# STLink.net
KiCad netlist of a schematic drawn in Altium Designer
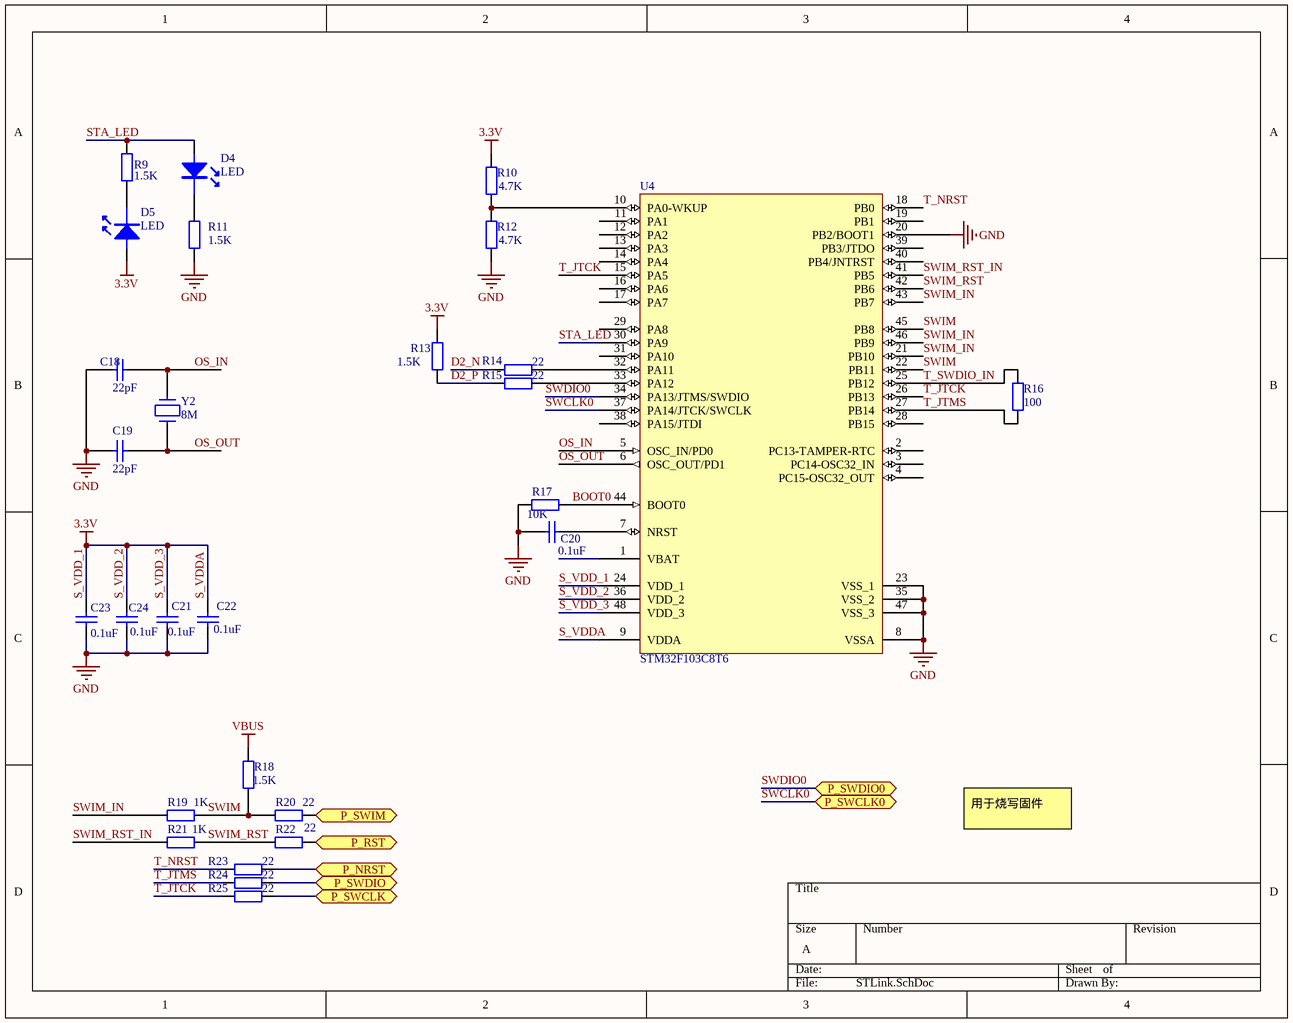
[diagram p0: STLink.SchDoc]

(export (version "E")
  (design (tool "Eeschema 10.0.6"))
  (components
    (comp (ref "C18")
      (value "22pF")
      (footprint "C-0603")
      (fields (field (name "Comment") "Cap"))
      (libsource (lib "WK_PCB") (part "Cap"))
    )
    (comp (ref "C19")
      (value "22pF")
      (footprint "C-0603")
      (fields (field (name "Comment") "Cap"))
      (libsource (lib "WK_PCB") (part "Cap"))
    )
    (comp (ref "C20")
      (value "0.1uF")
      (footprint "C-0603")
      (fields (field (name "Comment") "Cap"))
      (libsource (lib "WK_PCB") (part "Cap"))
    )
    (comp (ref "C21")
      (value "0.1uF")
      (footprint "C-0603")
      (description "Capacitor")
      (fields (field (name "Comment") "Cap") (field (name "PUBLISHER") "Altium Limited"))
      (libsource (lib "Miscellaneous Devices") (part "Cap"))
    )
    (comp (ref "C22")
      (value "0.1uF")
      (footprint "C-0603")
      (description "Capacitor")
      (fields (field (name "Comment") "Cap") (field (name "PUBLISHER") "Altium Limited"))
      (libsource (lib "Miscellaneous Devices") (part "Cap"))
    )
    (comp (ref "C23")
      (value "0.1uF")
      (footprint "C-0603")
      (description "Capacitor")
      (fields (field (name "Comment") "Cap") (field (name "PUBLISHER") "Altium Limited"))
      (libsource (lib "Miscellaneous Devices") (part "Cap"))
    )
    (comp (ref "C24")
      (value "0.1uF")
      (footprint "C-0603")
      (description "Capacitor")
      (fields (field (name "Comment") "Cap") (field (name "PUBLISHER") "Altium Limited"))
      (libsource (lib "Miscellaneous Devices") (part "Cap"))
    )
    (comp (ref "D4")
      (value "LED")
      (footprint "SMT_LED_0603")
      (description "LED 发光二极管")
      (libsource (lib "WK_PCB") (part "LED"))
    )
    (comp (ref "D5")
      (value "LED")
      (footprint "SMT_LED_0603")
      (description "LED 发光二极管")
      (libsource (lib "WK_PCB") (part "LED"))
    )
    (comp (ref "R9")
      (value "1.5K")
      (footprint "0603-1")
      (description "Resistor")
      (fields (field (name "Comment") "Res2") (field (name "PUBLISHER") "Altium Limited"))
      (libsource (lib "Miscellaneous Devices") (part "Res2"))
    )
    (comp (ref "R10")
      (value "4.7K")
      (footprint "0603-1")
      (description "Resistor")
      (fields (field (name "Comment") "Res2") (field (name "PUBLISHER") "Altium Limited"))
      (libsource (lib "Miscellaneous Devices") (part "Res2"))
    )
    (comp (ref "R11")
      (value "1.5K")
      (footprint "0603-1")
      (description "Resistor")
      (fields (field (name "Comment") "Res2") (field (name "PUBLISHER") "Altium Limited"))
      (libsource (lib "Miscellaneous Devices") (part "Res2"))
    )
    (comp (ref "R12")
      (value "4.7K")
      (footprint "0603-1")
      (description "Resistor")
      (fields (field (name "Comment") "Res2") (field (name "PUBLISHER") "Altium Limited"))
      (libsource (lib "Miscellaneous Devices") (part "Res2"))
    )
    (comp (ref "R13")
      (value "1.5K")
      (footprint "0603-1")
      (description "Resistor")
      (fields (field (name "Comment") "Res2") (field (name "PUBLISHER") "Altium Limited"))
      (libsource (lib "Miscellaneous Devices") (part "Res2"))
    )
    (comp (ref "R14")
      (value "22")
      (footprint "0603-1")
      (description "Resistor")
      (fields (field (name "Comment") "Res2") (field (name "PUBLISHER") "Altium Limited"))
      (libsource (lib "") (part "Res2_1"))
    )
    (comp (ref "R15")
      (value "22")
      (footprint "0603-1")
      (description "Resistor")
      (fields (field (name "Comment") "Res2") (field (name "PUBLISHER") "Altium Limited"))
      (libsource (lib "") (part "Res2_1"))
    )
    (comp (ref "R16")
      (value "100")
      (footprint "0603-1")
      (description "Resistor")
      (fields (field (name "Comment") "Res2") (field (name "PUBLISHER") "Altium Limited"))
      (libsource (lib "Miscellaneous Devices") (part "Res2"))
    )
    (comp (ref "R17")
      (value "10K")
      (footprint "0603-1")
      (description "Resistor")
      (fields (field (name "Comment") "Res2") (field (name "PUBLISHER") "Altium Limited"))
      (libsource (lib "") (part "Res2_1"))
    )
    (comp (ref "R18")
      (value "1.5K")
      (footprint "0603-1")
      (description "Resistor")
      (fields (field (name "Comment") "Res2") (field (name "PUBLISHER") "Altium Limited"))
      (libsource (lib "Miscellaneous Devices") (part "Res2"))
    )
    (comp (ref "R19")
      (value "1K")
      (footprint "0603-1")
      (description "Resistor")
      (fields (field (name "Comment") "Res2") (field (name "PUBLISHER") "Altium Limited"))
      (libsource (lib "") (part "Res2_1"))
    )
    (comp (ref "R20")
      (value "22")
      (footprint "0603-1")
      (description "Resistor")
      (fields (field (name "Comment") "Res2") (field (name "PUBLISHER") "Altium Limited"))
      (libsource (lib "") (part "Res2_1"))
    )
    (comp (ref "R21")
      (value "1K")
      (footprint "0603-1")
      (description "Resistor")
      (fields (field (name "Comment") "Res2") (field (name "PUBLISHER") "Altium Limited"))
      (libsource (lib "") (part "Res2_1"))
    )
    (comp (ref "R22")
      (value "22")
      (footprint "0603-1")
      (description "Resistor")
      (fields (field (name "Comment") "Res2") (field (name "PUBLISHER") "Altium Limited"))
      (libsource (lib "") (part "Res2_1"))
    )
    (comp (ref "R23")
      (value "22")
      (footprint "0603-1")
      (description "Resistor")
      (fields (field (name "Comment") "Res2") (field (name "PUBLISHER") "Altium Limited"))
      (libsource (lib "") (part "Res2_1"))
    )
    (comp (ref "R24")
      (value "22")
      (footprint "0603-1")
      (description "Resistor")
      (fields (field (name "Comment") "Res2") (field (name "PUBLISHER") "Altium Limited"))
      (libsource (lib "") (part "Res2_1"))
    )
    (comp (ref "R25")
      (value "22")
      (footprint "0603-1")
      (description "Resistor")
      (fields (field (name "Comment") "Res2") (field (name "PUBLISHER") "Altium Limited"))
      (libsource (lib "") (part "Res2_1"))
    )
    (comp (ref "U4")
      (value "STM32F103C8T6")
      (footprint "LQFP48_N")
      (description "STM32 ARM-based 32-bit MCU with 64 Kbytes Flash, 48-pin LQFP, Industrial Temperature")
      (fields (field (name "PUBLISHER") "Altium Limited"))
      (libsource (lib "ST Microcontroller 32-Bit STM32") (part "STM32F103C8T6"))
    )
    (comp (ref "Y2") (value "8M") (footprint "XAL5032 2-Leads") (libsource (lib "WK_PCB") (part "XTAL")))
  )
  (nets
    (net (code "1") (name "/BOOT0") (class "Default")
      (node (ref "R17") (pin "2") (pinfunction "2_2") (pintype "passive"))
      (node (ref "U4") (pin "44") (pinfunction "BOOT0_44") (pintype "input"))
    )
    (net (code "2") (name "/D2_N") (class "Default")
      (node (ref "R14") (pin "1") (pinfunction "1_1") (pintype "passive"))
    )
    (net (code "3") (name "/D2_P") (class "Default")
      (node (ref "R13") (pin "1") (pinfunction "1_1") (pintype "passive"))
      (node (ref "R15") (pin "1") (pinfunction "1_1") (pintype "passive"))
    )
    (net (code "4") (name "/OS_IN") (class "Default")
      (node (ref "C18") (pin "2") (pinfunction "2_2") (pintype "passive"))
      (node (ref "U4") (pin "5") (pinfunction "OSC_IN/PD0_5") (pintype "input"))
      (node (ref "Y2") (pin "2") (pinfunction "2_2") (pintype "passive"))
    )
    (net (code "5") (name "/OS_OUT") (class "Default")
      (node (ref "C19") (pin "2") (pinfunction "2_2") (pintype "passive"))
      (node (ref "U4") (pin "6") (pinfunction "OSC_OUT/PD1_6") (pintype "output"))
      (node (ref "Y2") (pin "1") (pinfunction "1_1") (pintype "passive"))
    )
    (net (code "6") (name "/P_NRST") (class "Default")
      (node (ref "R23") (pin "2") (pinfunction "2_2") (pintype "passive"))
    )
    (net (code "7") (name "/P_RST") (class "Default")
      (node (ref "R22") (pin "2") (pinfunction "2_2") (pintype "passive"))
    )
    (net (code "8") (name "/P_SWCLK") (class "Default")
      (node (ref "R25") (pin "2") (pinfunction "2_2") (pintype "passive"))
    )
    (net (code "9") (name "/P_SWDIO") (class "Default")
      (node (ref "R24") (pin "2") (pinfunction "2_2") (pintype "passive"))
    )
    (net (code "10") (name "/P_SWIM") (class "Default")
      (node (ref "R20") (pin "2") (pinfunction "2_2") (pintype "passive"))
    )
    (net (code "11") (name "/STA_LED") (class "Default")
      (node (ref "D4") (pin "1") (pinfunction "A_1") (pintype "passive"))
      (node (ref "R9") (pin "2") (pinfunction "2_2") (pintype "passive"))
      (node (ref "U4") (pin "30") (pinfunction "PA9_30") (pintype "bidirectional"))
    )
    (net (code "12") (name "/SWCLK0") (class "Default")
      (node (ref "U4") (pin "37") (pinfunction "PA14/JTCK/SWCLK_37") (pintype "bidirectional"))
    )
    (net (code "13") (name "/SWDIO0") (class "Default")
      (node (ref "U4") (pin "34") (pinfunction "PA13/JTMS/SWDIO_34") (pintype "bidirectional"))
    )
    (net (code "14") (name "/SWIM") (class "Default")
      (node (ref "R18") (pin "1") (pinfunction "1_1") (pintype "passive"))
      (node (ref "R19") (pin "2") (pinfunction "2_2") (pintype "passive"))
      (node (ref "R20") (pin "1") (pinfunction "1_1") (pintype "passive"))
      (node (ref "U4") (pin "22") (pinfunction "PB11_22") (pintype "bidirectional"))
      (node (ref "U4") (pin "45") (pinfunction "PB8_45") (pintype "bidirectional"))
    )
    (net (code "15") (name "/SWIM_IN") (class "Default")
      (node (ref "R19") (pin "1") (pinfunction "1_1") (pintype "passive"))
      (node (ref "U4") (pin "21") (pinfunction "PB10_21") (pintype "bidirectional"))
      (node (ref "U4") (pin "43") (pinfunction "PB7_43") (pintype "bidirectional"))
      (node (ref "U4") (pin "46") (pinfunction "PB9_46") (pintype "bidirectional"))
    )
    (net (code "16") (name "/SWIM_RST") (class "Default")
      (node (ref "R21") (pin "2") (pinfunction "2_2") (pintype "passive"))
      (node (ref "R22") (pin "1") (pinfunction "1_1") (pintype "passive"))
      (node (ref "U4") (pin "42") (pinfunction "PB6_42") (pintype "bidirectional"))
    )
    (net (code "17") (name "/SWIM_RST_IN") (class "Default")
      (node (ref "R21") (pin "1") (pinfunction "1_1") (pintype "passive"))
      (node (ref "U4") (pin "41") (pinfunction "PB5_41") (pintype "bidirectional"))
    )
    (net (code "18") (name "/T_JTCK") (class "Default")
      (node (ref "R25") (pin "1") (pinfunction "1_1") (pintype "passive"))
      (node (ref "U4") (pin "15") (pinfunction "PA5_15") (pintype "bidirectional"))
      (node (ref "U4") (pin "26") (pinfunction "PB13_26") (pintype "bidirectional"))
    )
    (net (code "19") (name "/T_JTMS") (class "Default")
      (node (ref "R16") (pin "1") (pinfunction "1_1") (pintype "passive"))
      (node (ref "R24") (pin "1") (pinfunction "1_1") (pintype "passive"))
      (node (ref "U4") (pin "27") (pinfunction "PB14_27") (pintype "bidirectional"))
    )
    (net (code "20") (name "/T_NRST") (class "Default")
      (node (ref "R23") (pin "1") (pinfunction "1_1") (pintype "passive"))
      (node (ref "U4") (pin "18") (pinfunction "PB0_18") (pintype "bidirectional"))
    )
    (net (code "21") (name "/T_SWDIO_IN") (class "Default")
      (node (ref "R16") (pin "2") (pinfunction "2_2") (pintype "passive"))
      (node (ref "U4") (pin "25") (pinfunction "PB12_25") (pintype "bidirectional"))
    )
    (net (code "22") (name "3.3V") (class "Default")
      (node (ref "C21") (pin "2") (pinfunction "2_2") (pintype "passive"))
      (node (ref "C22") (pin "2") (pinfunction "2_2") (pintype "passive"))
      (node (ref "C23") (pin "2") (pinfunction "2_2") (pintype "passive"))
      (node (ref "C24") (pin "2") (pinfunction "2_2") (pintype "passive"))
      (node (ref "D5") (pin "1") (pinfunction "A_1") (pintype "passive"))
      (node (ref "R10") (pin "2") (pinfunction "2_2") (pintype "passive"))
      (node (ref "R13") (pin "2") (pinfunction "2_2") (pintype "passive"))
      (node (ref "U4") (pin "24") (pinfunction "VDD_1_24") (pintype "power_in"))
      (node (ref "U4") (pin "36") (pinfunction "VDD_2_36") (pintype "power_in"))
      (node (ref "U4") (pin "48") (pinfunction "VDD_3_48") (pintype "power_in"))
      (node (ref "U4") (pin "9") (pinfunction "VDDA_9") (pintype "power_in"))
    )
    (net (code "23") (name "GND") (class "Default")
      (node (ref "C18") (pin "1") (pinfunction "1_1") (pintype "passive"))
      (node (ref "C19") (pin "1") (pinfunction "1_1") (pintype "passive"))
      (node (ref "C20") (pin "1") (pinfunction "1_1") (pintype "passive"))
      (node (ref "C21") (pin "1") (pinfunction "1_1") (pintype "passive"))
      (node (ref "C22") (pin "1") (pinfunction "1_1") (pintype "passive"))
      (node (ref "C23") (pin "1") (pinfunction "1_1") (pintype "passive"))
      (node (ref "C24") (pin "1") (pinfunction "1_1") (pintype "passive"))
      (node (ref "R11") (pin "1") (pinfunction "1_1") (pintype "passive"))
      (node (ref "R12") (pin "1") (pinfunction "1_1") (pintype "passive"))
      (node (ref "R17") (pin "1") (pinfunction "1_1") (pintype "passive"))
      (node (ref "U4") (pin "20") (pinfunction "PB2/BOOT1_20") (pintype "bidirectional"))
      (node (ref "U4") (pin "23") (pinfunction "VSS_1_23") (pintype "power_in"))
      (node (ref "U4") (pin "35") (pinfunction "VSS_2_35") (pintype "power_in"))
      (node (ref "U4") (pin "47") (pinfunction "VSS_3_47") (pintype "power_in"))
      (node (ref "U4") (pin "8") (pinfunction "VSSA_8") (pintype "power_in"))
    )
    (net (code "24") (name "Net-(D4-K)") (class "Default")
      (node (ref "D4") (pin "2") (pinfunction "K_2") (pintype "passive"))
      (node (ref "R11") (pin "2") (pinfunction "2_2") (pintype "passive"))
    )
    (net (code "25") (name "Net-(D5-K)") (class "Default")
      (node (ref "D5") (pin "2") (pinfunction "K_2") (pintype "passive"))
      (node (ref "R9") (pin "1") (pinfunction "1_1") (pintype "passive"))
    )
    (net (code "26") (name "Net-(U4-NRST)") (class "Default")
      (node (ref "C20") (pin "2") (pinfunction "2_2") (pintype "passive"))
      (node (ref "U4") (pin "7") (pinfunction "NRST_7") (pintype "bidirectional"))
    )
    (net (code "27") (name "Net-(U4-PA0-WKUP)") (class "Default")
      (node (ref "R10") (pin "1") (pinfunction "1_1") (pintype "passive"))
      (node (ref "R12") (pin "2") (pinfunction "2_2") (pintype "passive"))
      (node (ref "U4") (pin "10") (pinfunction "PA0-WKUP_10") (pintype "bidirectional"))
    )
    (net (code "28") (name "Net-(U4-PA11)") (class "Default")
      (node (ref "R14") (pin "2") (pinfunction "2_2") (pintype "passive"))
      (node (ref "U4") (pin "32") (pinfunction "PA11_32") (pintype "bidirectional"))
    )
    (net (code "29") (name "Net-(U4-PA12)") (class "Default")
      (node (ref "R15") (pin "2") (pinfunction "2_2") (pintype "passive"))
      (node (ref "U4") (pin "33") (pinfunction "PA12_33") (pintype "bidirectional"))
    )
    (net (code "30") (name "VBUS") (class "Default")
      (node (ref "R18") (pin "2") (pinfunction "2_2") (pintype "passive"))
    )
    (net (code "31") (name "unconnected-(U4-PA1-Pad11)") (class "Default")
      (node (ref "U4") (pin "11") (pinfunction "PA1_11") (pintype "bidirectional"))
    )
    (net (code "32") (name "unconnected-(U4-PA2-Pad12)") (class "Default")
      (node (ref "U4") (pin "12") (pinfunction "PA2_12") (pintype "bidirectional"))
    )
    (net (code "33") (name "unconnected-(U4-PA3-Pad13)") (class "Default")
      (node (ref "U4") (pin "13") (pinfunction "PA3_13") (pintype "bidirectional"))
    )
    (net (code "34") (name "unconnected-(U4-PA4-Pad14)") (class "Default")
      (node (ref "U4") (pin "14") (pinfunction "PA4_14") (pintype "bidirectional"))
    )
    (net (code "35") (name "unconnected-(U4-PA6-Pad16)") (class "Default")
      (node (ref "U4") (pin "16") (pinfunction "PA6_16") (pintype "bidirectional"))
    )
    (net (code "36") (name "unconnected-(U4-PA7-Pad17)") (class "Default")
      (node (ref "U4") (pin "17") (pinfunction "PA7_17") (pintype "bidirectional"))
    )
    (net (code "37") (name "unconnected-(U4-PA8-Pad29)") (class "Default")
      (node (ref "U4") (pin "29") (pinfunction "PA8_29") (pintype "bidirectional"))
    )
    (net (code "38") (name "unconnected-(U4-PA10-Pad31)") (class "Default")
      (node (ref "U4") (pin "31") (pinfunction "PA10_31") (pintype "bidirectional"))
    )
    (net (code "39") (name "unconnected-(U4-PA15{slash}JTDI-Pad38)") (class "Default")
      (node (ref "U4") (pin "38") (pinfunction "PA15/JTDI_38") (pintype "bidirectional"))
    )
    (net (code "40") (name "unconnected-(U4-PB1-Pad19)") (class "Default")
      (node (ref "U4") (pin "19") (pinfunction "PB1_19") (pintype "bidirectional"))
    )
    (net (code "41") (name "unconnected-(U4-PB3{slash}JTDO-Pad39)") (class "Default")
      (node (ref "U4") (pin "39") (pinfunction "PB3/JTDO_39") (pintype "bidirectional"))
    )
    (net (code "42") (name "unconnected-(U4-PB4{slash}JNTRST-Pad40)") (class "Default")
      (node (ref "U4") (pin "40") (pinfunction "PB4/JNTRST_40") (pintype "bidirectional"))
    )
    (net (code "43") (name "unconnected-(U4-PB15-Pad28)") (class "Default")
      (node (ref "U4") (pin "28") (pinfunction "PB15_28") (pintype "bidirectional"))
    )
    (net (code "44") (name "unconnected-(U4-PC13-TAMPER-RTC-Pad2)") (class "Default")
      (node (ref "U4") (pin "2") (pinfunction "PC13-TAMPER-RTC_2") (pintype "bidirectional"))
    )
    (net (code "45") (name "unconnected-(U4-PC14-OSC32_IN-Pad3)") (class "Default")
      (node (ref "U4") (pin "3") (pinfunction "PC14-OSC32_IN_3") (pintype "bidirectional"))
    )
    (net (code "46") (name "unconnected-(U4-PC15-OSC32_OUT-Pad4)") (class "Default")
      (node (ref "U4") (pin "4") (pinfunction "PC15-OSC32_OUT_4") (pintype "bidirectional"))
    )
    (net (code "47") (name "unconnected-(U4-VBAT-Pad1)") (class "Default")
      (node (ref "U4") (pin "1") (pinfunction "VBAT_1") (pintype "power_in"))
    )
  )
)
